# DroneRegul.net
KiCad netlist of a schematic drawn in Altium Designer
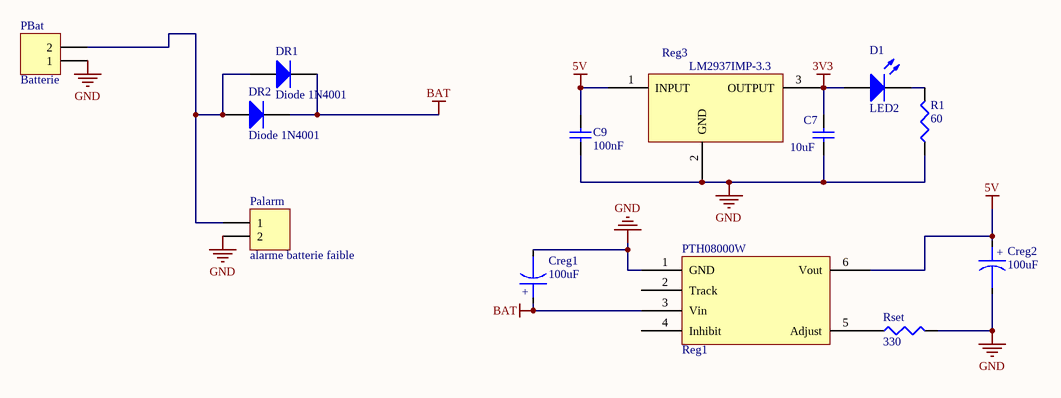
[diagram p0: DroneRegul.SchDoc]

(export (version "E")
  (design (tool "Eeschema 10.0.6"))
  (components
    (comp (ref "C7")
      (value "10uF")
      (footprint "C0805C")
      (description "Capacitor")
      (fields (field (name "Comment") "CAP") (field (name "PUBLISHER") "Altium Limited"))
      (libsource (lib "7Robot") (part "CAP"))
    )
    (comp (ref "C9")
      (value "100nF")
      (footprint "C0805C")
      (description "Capacitor")
      (fields (field (name "Comment") "CAP") (field (name "PUBLISHER") "Altium Limited"))
      (libsource (lib "7Robot") (part "CAP"))
    )
    (comp (ref "Creg1")
      (value "100uF")
      (footprint "RB.1/.3")
      (description "Polarized Capacitor")
      (fields (field (name "Comment") "CAP Pol"))
      (libsource (lib "7Robot") (part "CAP Pol"))
    )
    (comp (ref "Creg2")
      (value "100uF")
      (footprint "RB.1/.3")
      (description "Polarized Capacitor")
      (fields (field (name "Comment") "CAP Pol"))
      (libsource (lib "7Robot") (part "CAP Pol"))
    )
    (comp (ref "D1")
      (value "LED2")
      (footprint "LED1206G")
      (description "Typical RED, GREEN, YELLOW, AMBER GaAs LED")
      (fields (field (name "PUBLISHER") "Altium Limited"))
      (libsource (lib "7Robot") (part "LED2"))
    )
    (comp (ref "DR1")
      (value "Diode 1N4001")
      (footprint "DO-41")
      (description "1 Amp General Purpose Rectifier")
      (fields (field (name "PUBLISHER") "Altium Limited"))
      (libsource (lib "Miscellaneous Devices") (part "Diode 1N4001"))
    )
    (comp (ref "DR2")
      (value "Diode 1N4001")
      (footprint "DO-41")
      (description "1 Amp General Purpose Rectifier")
      (fields (field (name "PUBLISHER") "Altium Limited"))
      (libsource (lib "Miscellaneous Devices") (part "Diode 1N4001"))
    )
    (comp (ref "Palarm")
      (value "alarme batterie faible")
      (footprint "HDR1X2")
      (description "Header, 2-Pin")
      (fields (field (name "PUBLISHER") "Altium Limited"))
      (libsource (lib "7Robot") (part "Header 2"))
    )
    (comp (ref "PBat")
      (value "Batterie")
      (footprint "TERM2W-3.5")
      (description "Header, 2-Pin")
      (fields (field (name "PUBLISHER") "Altium Limited"))
      (libsource (lib "") (part "Header 2_1"))
    )
    (comp (ref "PTH08000W")
      (value "Reg1")
      (footprint "PTH08000W")
      (libsource (lib "7Robot") (part "PTH08000W"))
    )
    (comp (ref "R1")
      (value "60")
      (footprint "C0805R")
      (description "Resistor")
      (fields (field (name "Comment") "RES") (field (name "PUBLISHER") "Altium Limited"))
      (libsource (lib "7Robot") (part "RES"))
    )
    (comp (ref "Reg3")
      (value "LM2937IMP-3.3")
      (footprint "TO-220-AB")
      (description "500 mA Low Dropout Regulator")
      (libsource (lib "7Robot") (part "LM2937IMP-3.3"))
    )
    (comp (ref "Rset")
      (value "330")
      (footprint "C0805R")
      (description "Resistor")
      (fields (field (name "Comment") "RES") (field (name "PUBLISHER") "Altium Limited"))
      (libsource (lib "7Robot") (part "RES"))
    )
  )
  (nets
    (net (code "1") (name "3V3") (class "Default")
      (node (ref "C7") (pin "2") (pinfunction "2_2") (pintype "passive"))
      (node (ref "D1") (pin "1") (pinfunction "A_1") (pintype "passive"))
      (node (ref "Reg3") (pin "3") (pinfunction "OUTPUT_3") (pintype "power_in"))
    )
    (net (code "2") (name "5V") (class "Default")
      (node (ref "C9") (pin "1") (pinfunction "1_1") (pintype "passive"))
      (node (ref "Creg2") (pin "1") (pinfunction "1_1") (pintype "passive"))
      (node (ref "PTH08000W") (pin "6") (pinfunction "Vout_6") (pintype "passive"))
      (node (ref "Reg3") (pin "1") (pinfunction "INPUT_1") (pintype "power_in"))
    )
    (net (code "3") (name "BAT") (class "Default")
      (node (ref "Creg1") (pin "1") (pinfunction "1_1") (pintype "passive"))
      (node (ref "DR1") (pin "2") (pinfunction "K_2") (pintype "passive"))
      (node (ref "DR2") (pin "2") (pinfunction "K_2") (pintype "passive"))
      (node (ref "PTH08000W") (pin "3") (pinfunction "Vin_3") (pintype "passive"))
    )
    (net (code "4") (name "GND") (class "Default")
      (node (ref "C7") (pin "1") (pinfunction "1_1") (pintype "passive"))
      (node (ref "C9") (pin "2") (pinfunction "2_2") (pintype "passive"))
      (node (ref "Creg1") (pin "2") (pinfunction "2_2") (pintype "passive"))
      (node (ref "Creg2") (pin "2") (pinfunction "2_2") (pintype "passive"))
      (node (ref "PBat") (pin "1") (pinfunction "1_1") (pintype "passive"))
      (node (ref "PTH08000W") (pin "1") (pinfunction "GND_1") (pintype "passive"))
      (node (ref "Palarm") (pin "2") (pinfunction "2_2") (pintype "passive"))
      (node (ref "R1") (pin "1") (pinfunction "1_1") (pintype "passive"))
      (node (ref "Reg3") (pin "2") (pinfunction "GND_2") (pintype "power_in"))
      (node (ref "Rset") (pin "2") (pinfunction "2_2") (pintype "passive"))
    )
    (net (code "5") (name "Net-(D1-K)") (class "Default")
      (node (ref "D1") (pin "2") (pinfunction "K_2") (pintype "passive"))
      (node (ref "R1") (pin "2") (pinfunction "2_2") (pintype "passive"))
    )
    (net (code "6") (name "Net-(DR1-A)") (class "Default")
      (node (ref "DR1") (pin "1") (pinfunction "A_1") (pintype "passive"))
      (node (ref "DR2") (pin "1") (pinfunction "A_1") (pintype "passive"))
      (node (ref "PBat") (pin "2") (pinfunction "2_2") (pintype "passive"))
      (node (ref "Palarm") (pin "1") (pinfunction "1_1") (pintype "passive"))
    )
    (net (code "7") (name "Net-(PTH08000W-Adjust)") (class "Default")
      (node (ref "PTH08000W") (pin "5") (pinfunction "Adjust_5") (pintype "passive"))
      (node (ref "Rset") (pin "1") (pinfunction "1_1") (pintype "passive"))
    )
    (net (code "8") (name "unconnected-(PTH08000W-Inhibit-Pad4)") (class "Default")
      (node (ref "PTH08000W") (pin "4") (pinfunction "Inhibit_4") (pintype "passive"))
    )
    (net (code "9") (name "unconnected-(PTH08000W-Track-Pad2)") (class "Default")
      (node (ref "PTH08000W") (pin "2") (pinfunction "Track_2") (pintype "passive"))
    )
  )
)
